# RB_Power.net
KiCad netlist of a schematic drawn in Altium Designer
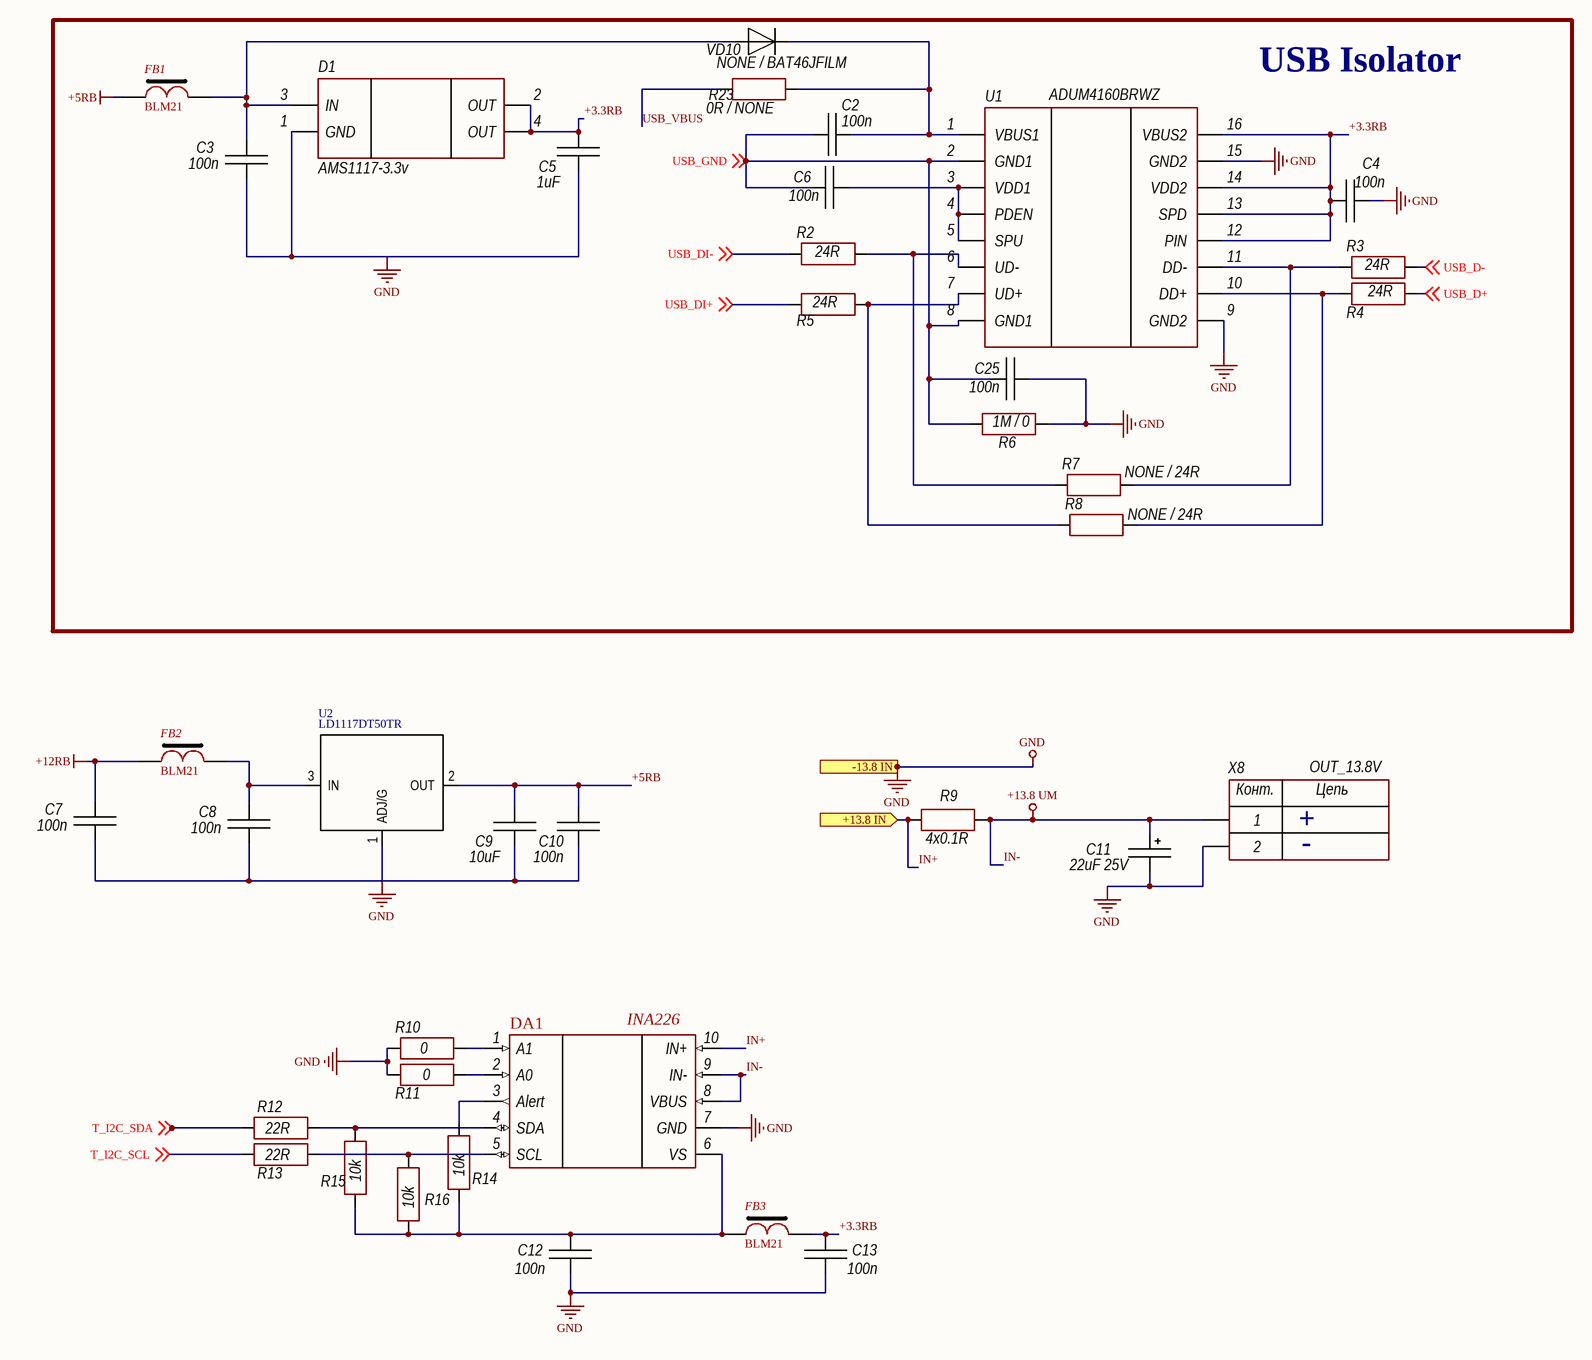
[diagram p0: RB_Power.SchDoc]

(export (version "E")
  (design (tool "Eeschema 10.0.6"))
  (components
    (comp (ref "C2")
      (value "100n")
      (footprint "standard:CH0805C")
      (libsource (lib "Discrete") (part "Capacitor"))
    )
    (comp (ref "C3") (value "100n") (footprint "standard:CH0805C") (libsource (lib "") (part "Capacitor_1")))
    (comp (ref "C4")
      (value "100n")
      (footprint "standard:CH0805C")
      (libsource (lib "Discrete") (part "Capacitor"))
    )
    (comp (ref "C5") (value "1uF") (footprint "standard:CH0805C") (libsource (lib "") (part "Capacitor_2")))
    (comp (ref "C6") (value "100n") (footprint "standard:CH0805C") (libsource (lib "") (part "Capacitor_3")))
    (comp (ref "C7")
      (value "100n")
      (footprint "standard:CH0805C")
      (libsource (lib "Discrete") (part "Capacitor"))
    )
    (comp (ref "C8")
      (value "100n")
      (footprint "standard:CH0805C")
      (libsource (lib "Discrete") (part "Capacitor"))
    )
    (comp (ref "C9")
      (value "10uF")
      (footprint "standard:CH0805C")
      (libsource (lib "Discrete") (part "Capacitor"))
    )
    (comp (ref "C10")
      (value "100n")
      (footprint "standard:CH0805C")
      (libsource (lib "Discrete") (part "Capacitor"))
    )
    (comp (ref "C11")
      (value "22uF 25V")
      (footprint "standard:TANTAL_D")
      (libsource (lib "Discrete") (part "TantalCap"))
    )
    (comp (ref "C12")
      (value "100n")
      (footprint "standard:CH0805C")
      (libsource (lib "Discrete") (part "Capacitor"))
    )
    (comp (ref "C13")
      (value "100n")
      (footprint "standard:CH0805C")
      (libsource (lib "Discrete") (part "Capacitor"))
    )
    (comp (ref "C25")
      (value "100n")
      (footprint "standard:CH0805C")
      (libsource (lib "Discrete") (part "Capacitor"))
    )
    (comp (ref "D1")
      (value "AMS1117-3.3v")
      (footprint "standard:SOT223")
      (description "LDO")
      (fields (field (name "MANUFACTURER") "ON Semiconductor"))
      (libsource (lib "Power Supplies") (part "NCP1117LPST50T3G"))
    )
    (comp (ref "DA1") (value "INA226") (footprint "10-TSSOP") (libsource (lib "Digital") (part "INA226")))
    (comp (ref "FB1") (value "BLM21") (footprint "CH0805L") (libsource (lib "Discrete") (part "FB-1")))
    (comp (ref "FB2") (value "BLM21") (footprint "CH0805L") (libsource (lib "Discrete") (part "FB-1")))
    (comp (ref "FB3") (value "BLM21") (footprint "CH0805L") (libsource (lib "Discrete") (part "FB-1")))
    (comp (ref "R2")
      (value "24R")
      (footprint "standard:CH0805R")
      (libsource (lib "Discrete") (part "Resistor"))
    )
    (comp (ref "R3")
      (value "24R")
      (footprint "standard:CH0805R")
      (libsource (lib "Discrete") (part "Resistor"))
    )
    (comp (ref "R4")
      (value "24R")
      (footprint "standard:CH0805R")
      (libsource (lib "Discrete") (part "Resistor"))
    )
    (comp (ref "R5")
      (value "24R")
      (footprint "standard:CH0805R")
      (libsource (lib "Discrete") (part "Resistor"))
    )
    (comp (ref "R6")
      (value "1M / 0")
      (footprint "standard:CH0805R")
      (libsource (lib "Discrete") (part "Resistor"))
    )
    (comp (ref "R7")
      (value "NONE / 24R")
      (footprint "standard:CH0805R")
      (libsource (lib "Discrete") (part "Resistor"))
    )
    (comp (ref "R8")
      (value "NONE / 24R")
      (footprint "standard:CH0805R")
      (libsource (lib "Discrete") (part "Resistor"))
    )
    (comp (ref "R9") (value "4x0.1R") (footprint "R-DIP") (libsource (lib "Discrete") (part "Resistor")))
    (comp (ref "R10")
      (value "0")
      (footprint "standard:CH0805R")
      (libsource (lib "Discrete") (part "Resistor"))
    )
    (comp (ref "R11")
      (value "0")
      (footprint "standard:CH0805R")
      (libsource (lib "Discrete") (part "Resistor"))
    )
    (comp (ref "R12")
      (value "22R")
      (footprint "standard:CH0805R")
      (libsource (lib "Discrete") (part "Resistor"))
    )
    (comp (ref "R13")
      (value "22R")
      (footprint "standard:CH0805R")
      (libsource (lib "Discrete") (part "Resistor"))
    )
    (comp (ref "R14") (value "10k") (footprint "standard:CH0805R") (libsource (lib "") (part "Resistor_1")))
    (comp (ref "R15") (value "10k") (footprint "standard:CH0805R") (libsource (lib "") (part "Resistor_1")))
    (comp (ref "R16") (value "10k") (footprint "standard:CH0805R") (libsource (lib "") (part "Resistor_1")))
    (comp (ref "R23")
      (value "0R / NONE")
      (footprint "standard:CH0805R")
      (libsource (lib "Discrete") (part "Resistor"))
    )
    (comp (ref "U1")
      (value "ADUM4160BRWZ")
      (footprint "16-SOIC(W)")
      (description "Isolator USB")
      (fields (field (name "MANUFACTURER") "Analog Devices Inc."))
      (libsource (lib "Analog") (part "ADUM3160BRWZ"))
    )
    (comp (ref "U2")
      (value "LD1117DT50TR")
      (footprint "TO-263-3(123)")
      (libsource (lib "Power Supplies") (part "LM1084"))
    )
    (comp (ref "VD10")
      (value "NONE / BAT46JFILM")
      (footprint "standard:SOD323")
      (libsource (lib "Diods") (part "Diod"))
    )
    (comp (ref "X8")
      (value "OUT_13.8V")
      (footprint "custom:CON: WF-02")
      (libsource (lib "Connectors") (part "2-Connector"))
    )
  )
  (nets
    (net (code "1") (name "+5RB") (class "Default")
      (node (ref "C10") (pin "2") (pinfunction "2_2") (pintype "power_in"))
      (node (ref "C9") (pin "2") (pinfunction "2_2") (pintype "power_in"))
      (node (ref "FB1") (pin "2") (pinfunction "2_2") (pintype "passive"))
      (node (ref "U2") (pin "2") (pinfunction "OUT_2") (pintype "passive"))
    )
    (net (code "2") (name "+12RB") (class "Default")
      (node (ref "C7") (pin "2") (pinfunction "2_2") (pintype "power_in"))
      (node (ref "FB2") (pin "2") (pinfunction "2_2") (pintype "passive"))
    )
    (net (code "3") (name "+13.8 UM") (class "Default")
      (node (ref "C11") (pin "1") (pinfunction "1_1") (pintype "power_in"))
      (node (ref "DA1") (pin "8") (pinfunction "VBUS_8") (pintype "input"))
      (node (ref "DA1") (pin "9") (pinfunction "IN-_9") (pintype "input"))
      (node (ref "R9") (pin "2") (pinfunction "2_2") (pintype "passive"))
      (node (ref "X8") (pin "1") (pinfunction "1_1") (pintype "passive"))
    )
    (net (code "4") (name "/+3.3RB") (class "Default")
      (node (ref "C13") (pin "2") (pinfunction "2_2") (pintype "power_in"))
      (node (ref "C4") (pin "1") (pinfunction "1_1") (pintype "power_in"))
      (node (ref "C5") (pin "2") (pinfunction "2_2") (pintype "power_in"))
      (node (ref "D1") (pin "2") (pinfunction "OUT_2") (pintype "passive"))
      (node (ref "D1") (pin "4") (pinfunction "OUT_4") (pintype "passive"))
      (node (ref "FB3") (pin "1") (pinfunction "1_1") (pintype "passive"))
      (node (ref "U1") (pin "12") (pinfunction "PIN_12") (pintype "passive"))
      (node (ref "U1") (pin "13") (pinfunction "SPD_13") (pintype "passive"))
      (node (ref "U1") (pin "14") (pinfunction "VDD2_14") (pintype "passive"))
      (node (ref "U1") (pin "16") (pinfunction "VBUS2_16") (pintype "passive"))
    )
    (net (code "5") (name "/IN+") (class "Default")
      (node (ref "DA1") (pin "10") (pinfunction "IN+_10") (pintype "input"))
      (node (ref "R9") (pin "1") (pinfunction "1_1") (pintype "passive"))
    )
    (net (code "6") (name "/USB_VBUS") (class "Default")
      (node (ref "R23") (pin "1") (pinfunction "1_1") (pintype "passive"))
    )
    (net (code "7") (name "GND") (class "Default")
      (node (ref "C10") (pin "1") (pinfunction "1_1") (pintype "power_in"))
      (node (ref "C11") (pin "2") (pinfunction "2_2") (pintype "power_in"))
      (node (ref "C12") (pin "1") (pinfunction "1_1") (pintype "power_in"))
      (node (ref "C13") (pin "1") (pinfunction "1_1") (pintype "power_in"))
      (node (ref "C25") (pin "2") (pinfunction "2_2") (pintype "power_in"))
      (node (ref "C3") (pin "1") (pinfunction "1_1") (pintype "power_in"))
      (node (ref "C4") (pin "2") (pinfunction "2_2") (pintype "power_in"))
      (node (ref "C5") (pin "1") (pinfunction "1_1") (pintype "power_in"))
      (node (ref "C7") (pin "1") (pinfunction "1_1") (pintype "power_in"))
      (node (ref "C8") (pin "1") (pinfunction "1_1") (pintype "power_in"))
      (node (ref "C9") (pin "1") (pinfunction "1_1") (pintype "power_in"))
      (node (ref "D1") (pin "1") (pinfunction "GND_1") (pintype "passive"))
      (node (ref "DA1") (pin "7") (pinfunction "GND_7") (pintype "power_in"))
      (node (ref "R10") (pin "1") (pinfunction "1_1") (pintype "passive"))
      (node (ref "R11") (pin "1") (pinfunction "1_1") (pintype "passive"))
      (node (ref "R6") (pin "2") (pinfunction "2_2") (pintype "passive"))
      (node (ref "U1") (pin "15") (pinfunction "GND2_15") (pintype "passive"))
      (node (ref "U1") (pin "9") (pinfunction "GND2_9") (pintype "passive"))
      (node (ref "U2") (pin "1") (pinfunction "ADJ/G_1") (pintype "passive"))
      (node (ref "X8") (pin "2") (pinfunction "2_2") (pintype "passive"))
    )
    (net (code "8") (name "Net-(D1-IN)") (class "Default")
      (node (ref "C3") (pin "2") (pinfunction "2_2") (pintype "power_in"))
      (node (ref "D1") (pin "3") (pinfunction "IN_3") (pintype "power_in"))
      (node (ref "FB1") (pin "1") (pinfunction "1_1") (pintype "passive"))
      (node (ref "VD10") (pin "1") (pinfunction "1_1") (pintype "passive"))
    )
    (net (code "9") (name "Net-(DA1-A0)") (class "Default")
      (node (ref "DA1") (pin "2") (pinfunction "A0_2") (pintype "input"))
      (node (ref "R11") (pin "2") (pinfunction "2_2") (pintype "passive"))
    )
    (net (code "10") (name "Net-(DA1-A1)") (class "Default")
      (node (ref "DA1") (pin "1") (pinfunction "A1_1") (pintype "input"))
      (node (ref "R10") (pin "2") (pinfunction "2_2") (pintype "passive"))
    )
    (net (code "11") (name "Net-(DA1-Alert)") (class "Default")
      (node (ref "DA1") (pin "3") (pinfunction "Alert_3") (pintype "output"))
      (node (ref "R14") (pin "2") (pinfunction "2_2") (pintype "passive"))
    )
    (net (code "12") (name "Net-(DA1-SCL)") (class "Default")
      (node (ref "DA1") (pin "5") (pinfunction "SCL_5") (pintype "bidirectional"))
      (node (ref "R13") (pin "2") (pinfunction "2_2") (pintype "passive"))
      (node (ref "R16") (pin "2") (pinfunction "2_2") (pintype "passive"))
    )
    (net (code "13") (name "Net-(DA1-SDA)") (class "Default")
      (node (ref "DA1") (pin "4") (pinfunction "SDA_4") (pintype "bidirectional"))
      (node (ref "R12") (pin "2") (pinfunction "2_2") (pintype "passive"))
      (node (ref "R15") (pin "2") (pinfunction "2_2") (pintype "passive"))
    )
    (net (code "14") (name "Net-(DA1-VS)") (class "Default")
      (node (ref "C12") (pin "2") (pinfunction "2_2") (pintype "power_in"))
      (node (ref "DA1") (pin "6") (pinfunction "VS_6") (pintype "power_in"))
      (node (ref "FB3") (pin "2") (pinfunction "2_2") (pintype "passive"))
      (node (ref "R14") (pin "1") (pinfunction "1_1") (pintype "passive"))
      (node (ref "R15") (pin "1") (pinfunction "1_1") (pintype "passive"))
      (node (ref "R16") (pin "1") (pinfunction "1_1") (pintype "passive"))
    )
    (net (code "15") (name "Net-(U1-DD+)") (class "Default")
      (node (ref "R4") (pin "1") (pinfunction "1_1") (pintype "passive"))
      (node (ref "R8") (pin "2") (pinfunction "2_2") (pintype "passive"))
      (node (ref "U1") (pin "10") (pinfunction "DD+_10") (pintype "passive"))
    )
    (net (code "16") (name "Net-(U1-DD-)") (class "Default")
      (node (ref "R3") (pin "1") (pinfunction "1_1") (pintype "passive"))
      (node (ref "R7") (pin "2") (pinfunction "2_2") (pintype "passive"))
      (node (ref "U1") (pin "11") (pinfunction "DD-_11") (pintype "passive"))
    )
    (net (code "17") (name "Net-(U1-PDEN)") (class "Default")
      (node (ref "C6") (pin "2") (pinfunction "2_2") (pintype "power_in"))
      (node (ref "U1") (pin "3") (pinfunction "VDD1_3") (pintype "passive"))
      (node (ref "U1") (pin "4") (pinfunction "PDEN_4") (pintype "passive"))
      (node (ref "U1") (pin "5") (pinfunction "SPU_5") (pintype "passive"))
    )
    (net (code "18") (name "Net-(U1-UD+)") (class "Default")
      (node (ref "R5") (pin "2") (pinfunction "2_2") (pintype "passive"))
      (node (ref "R8") (pin "1") (pinfunction "1_1") (pintype "passive"))
      (node (ref "U1") (pin "7") (pinfunction "UD+_7") (pintype "passive"))
    )
    (net (code "19") (name "Net-(U1-UD-)") (class "Default")
      (node (ref "R2") (pin "2") (pinfunction "2_2") (pintype "passive"))
      (node (ref "R7") (pin "1") (pinfunction "1_1") (pintype "passive"))
      (node (ref "U1") (pin "6") (pinfunction "UD-_6") (pintype "passive"))
    )
    (net (code "20") (name "Net-(U1-VBUS1)") (class "Default")
      (node (ref "C2") (pin "2") (pinfunction "2_2") (pintype "power_in"))
      (node (ref "R23") (pin "2") (pinfunction "2_2") (pintype "passive"))
      (node (ref "U1") (pin "1") (pinfunction "VBUS1_1") (pintype "passive"))
      (node (ref "VD10") (pin "2") (pinfunction "2_2") (pintype "passive"))
    )
    (net (code "21") (name "Net-(U2-IN)") (class "Default")
      (node (ref "C8") (pin "2") (pinfunction "2_2") (pintype "power_in"))
      (node (ref "FB2") (pin "1") (pinfunction "1_1") (pintype "passive"))
      (node (ref "U2") (pin "3") (pinfunction "IN_3") (pintype "passive"))
    )
    (net (code "22") (name "T_I2C_SCL") (class "Default")
      (node (ref "R13") (pin "1") (pinfunction "1_1") (pintype "passive"))
    )
    (net (code "23") (name "T_I2C_SDA") (class "Default")
      (node (ref "R12") (pin "1") (pinfunction "1_1") (pintype "passive"))
    )
    (net (code "24") (name "USB_D+") (class "Default")
      (node (ref "R4") (pin "2") (pinfunction "2_2") (pintype "passive"))
    )
    (net (code "25") (name "USB_D-") (class "Default")
      (node (ref "R3") (pin "2") (pinfunction "2_2") (pintype "passive"))
    )
    (net (code "26") (name "USB_DI+") (class "Default")
      (node (ref "R5") (pin "1") (pinfunction "1_1") (pintype "passive"))
    )
    (net (code "27") (name "USB_DI-") (class "Default")
      (node (ref "R2") (pin "1") (pinfunction "1_1") (pintype "passive"))
    )
    (net (code "28") (name "USB_GND") (class "Default")
      (node (ref "C2") (pin "1") (pinfunction "1_1") (pintype "power_in"))
      (node (ref "C25") (pin "1") (pinfunction "1_1") (pintype "power_in"))
      (node (ref "C6") (pin "1") (pinfunction "1_1") (pintype "power_in"))
      (node (ref "R6") (pin "1") (pinfunction "1_1") (pintype "passive"))
      (node (ref "U1") (pin "2") (pinfunction "GND1_2") (pintype "passive"))
      (node (ref "U1") (pin "8") (pinfunction "GND1_8") (pintype "passive"))
    )
  )
)
